# Bandpass.net
KiCad netlist of a schematic drawn in Altium Designer
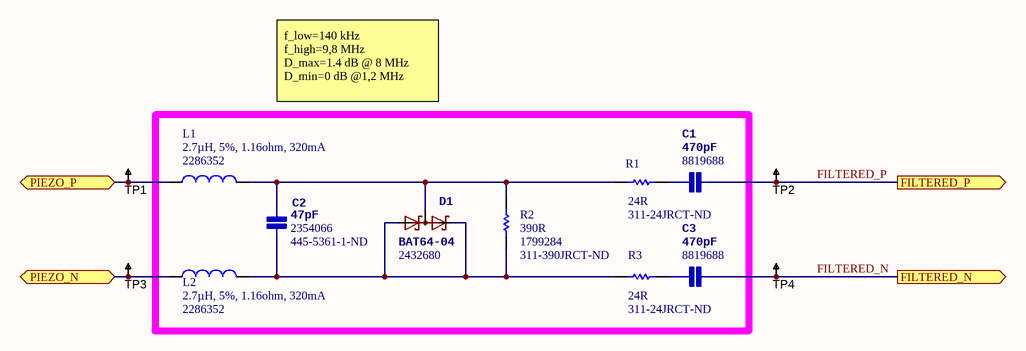
[diagram p0: Bandpass.SchDoc]

(export (version "E")
  (design (tool "Eeschema 10.0.6"))
  (components
    (comp (ref "C1")
      (value "470pF")
      (footprint "0402[1005]")
      (description "Cap")
      (fields (field (name "SUPPLIER PART NUMBER 1") "8819688"))
      (libsource (lib "") (part "Capacitor_1"))
    )
    (comp (ref "C2")
      (value "47pF")
      (footprint "0402[1005]")
      (description "Cap")
      (fields
        (field (name "SUPPLIER PART NUMBER 1") "445-5361-1-ND")
        (field (name "SUPPLIER PART NUMBER 2") "2354066")
      )
      (libsource (lib "Components") (part "Capacitor"))
    )
    (comp (ref "C3")
      (value "470pF")
      (footprint "0402[1005]")
      (description "Cap")
      (fields (field (name "SUPPLIER PART NUMBER 1") "8819688"))
      (libsource (lib "") (part "Capacitor_1"))
    )
    (comp (ref "D1")
      (value "BAT64-04")
      (footprint "SOT23-3")
      (description "Silicon Schottky Diodes")
      (fields (field (name "SUPPLIER PART NUMBER 1") "2432680"))
      (libsource (lib "Components") (part "BAT64-04"))
    )
    (comp (ref "L1")
      (value "2.7µH, 5%, 1.16ohm, 320mA")
      (footprint "WE0805")
      (description "Inductor")
      (fields (field (name "SUPPLIER PART NUMBER 1") "2286352") (field (name "PUBLISHER") "Altium Limited"))
      (libsource (lib "Components") (part "Inductor"))
    )
    (comp (ref "L2")
      (value "2.7µH, 5%, 1.16ohm, 320mA")
      (footprint "WE0805")
      (description "Inductor")
      (fields (field (name "SUPPLIER PART NUMBER 1") "2286352") (field (name "PUBLISHER") "Altium Limited"))
      (libsource (lib "Components") (part "Inductor"))
    )
    (comp (ref "R1")
      (value "24R")
      (footprint "0402[1005]")
      (description "Resistor")
      (fields
        (field (name "SUPPLIER PART NUMBER 1") "311-24JRCT-ND")
        (field (name "PUBLISHER") "Altium Limited")
      )
      (libsource (lib "Components") (part "Resistor"))
    )
    (comp (ref "R2")
      (value "390R")
      (footprint "0402[1005]")
      (description "Resistor")
      (fields
        (field (name "SUPPLIER PART NUMBER 1") "1799284")
        (field (name "SUPPLIER PART NUMBER 2") "311-390JRCT-ND")
        (field (name "PUBLISHER") "Altium Limited")
      )
      (libsource (lib "Components") (part "Resistor"))
    )
    (comp (ref "R3")
      (value "24R")
      (footprint "0402[1005]")
      (description "Resistor")
      (fields
        (field (name "SUPPLIER PART NUMBER 1") "311-24JRCT-ND")
        (field (name "PUBLISHER") "Altium Limited")
      )
      (libsource (lib "Components") (part "Resistor"))
    )
    (comp (ref "TP1")
      (value "TESTPOINT_THT_MINI")
      (footprint "TP-THT-MINI")
      (description "Test Point PCB mount Miniature White")
      (fields (field (name "PBL PART NUMBER") "3100-567"))
      (libsource (lib "USD Parts") (part "TESTPOINT_THT_MINI"))
    )
    (comp (ref "TP2")
      (value "TESTPOINT_THT_MINI")
      (footprint "TP-THT-MINI")
      (description "Test Point PCB mount Miniature White")
      (fields (field (name "PBL PART NUMBER") "3100-567"))
      (libsource (lib "USD Parts") (part "TESTPOINT_THT_MINI"))
    )
    (comp (ref "TP3")
      (value "TESTPOINT_THT_MINI")
      (footprint "TP-THT-MINI")
      (description "Test Point PCB mount Miniature White")
      (fields (field (name "PBL PART NUMBER") "3100-567"))
      (libsource (lib "USD Parts") (part "TESTPOINT_THT_MINI"))
    )
    (comp (ref "TP4")
      (value "TESTPOINT_THT_MINI")
      (footprint "TP-THT-MINI")
      (description "Test Point PCB mount Miniature White")
      (fields (field (name "PBL PART NUMBER") "3100-567"))
      (libsource (lib "USD Parts") (part "TESTPOINT_THT_MINI"))
    )
  )
  (nets
    (net (code "1") (name "/FILTERED_N") (class "Default")
      (node (ref "C3") (pin "2") (pinfunction "P$2_2") (pintype "passive"))
      (node (ref "TP4") (pin "1") (pintype "passive"))
    )
    (net (code "2") (name "/FILTERED_P") (class "Default")
      (node (ref "C1") (pin "2") (pinfunction "P$2_2") (pintype "passive"))
      (node (ref "TP2") (pin "1") (pintype "passive"))
    )
    (net (code "3") (name "/PIEZO_N") (class "Default")
      (node (ref "L2") (pin "1") (pinfunction "1_1") (pintype "passive"))
      (node (ref "TP3") (pin "1") (pintype "passive"))
    )
    (net (code "4") (name "/PIEZO_P") (class "Default")
      (node (ref "L1") (pin "1") (pinfunction "1_1") (pintype "passive"))
      (node (ref "TP1") (pin "1") (pintype "passive"))
    )
    (net (code "5") (name "Net-(C1-P$1)") (class "Default")
      (node (ref "C1") (pin "1") (pinfunction "P$1_1") (pintype "passive"))
      (node (ref "R1") (pin "2") (pinfunction "2_2") (pintype "passive"))
    )
    (net (code "6") (name "Net-(C2-P$1)") (class "Default")
      (node (ref "C2") (pin "1") (pinfunction "P$1_1") (pintype "passive"))
      (node (ref "D1") (pin "3") (pinfunction "C1A2_3") (pintype "passive"))
      (node (ref "L1") (pin "2") (pinfunction "2_2") (pintype "passive"))
      (node (ref "R1") (pin "1") (pinfunction "1_1") (pintype "passive"))
      (node (ref "R2") (pin "1") (pinfunction "1_1") (pintype "passive"))
    )
    (net (code "7") (name "Net-(C2-P$2)") (class "Default")
      (node (ref "C2") (pin "2") (pinfunction "P$2_2") (pintype "passive"))
      (node (ref "D1") (pin "1") (pinfunction "A1_1") (pintype "passive"))
      (node (ref "D1") (pin "2") (pinfunction "C2_2") (pintype "passive"))
      (node (ref "L2") (pin "2") (pinfunction "2_2") (pintype "passive"))
      (node (ref "R2") (pin "2") (pinfunction "2_2") (pintype "passive"))
      (node (ref "R3") (pin "1") (pinfunction "1_1") (pintype "passive"))
    )
    (net (code "8") (name "Net-(C3-P$1)") (class "Default")
      (node (ref "C3") (pin "1") (pinfunction "P$1_1") (pintype "passive"))
      (node (ref "R3") (pin "2") (pinfunction "2_2") (pintype "passive"))
    )
  )
)
